# TJMakes_Xiao_Adapter.net
KiCad netlist of a schematic drawn in EasyEDA Pro
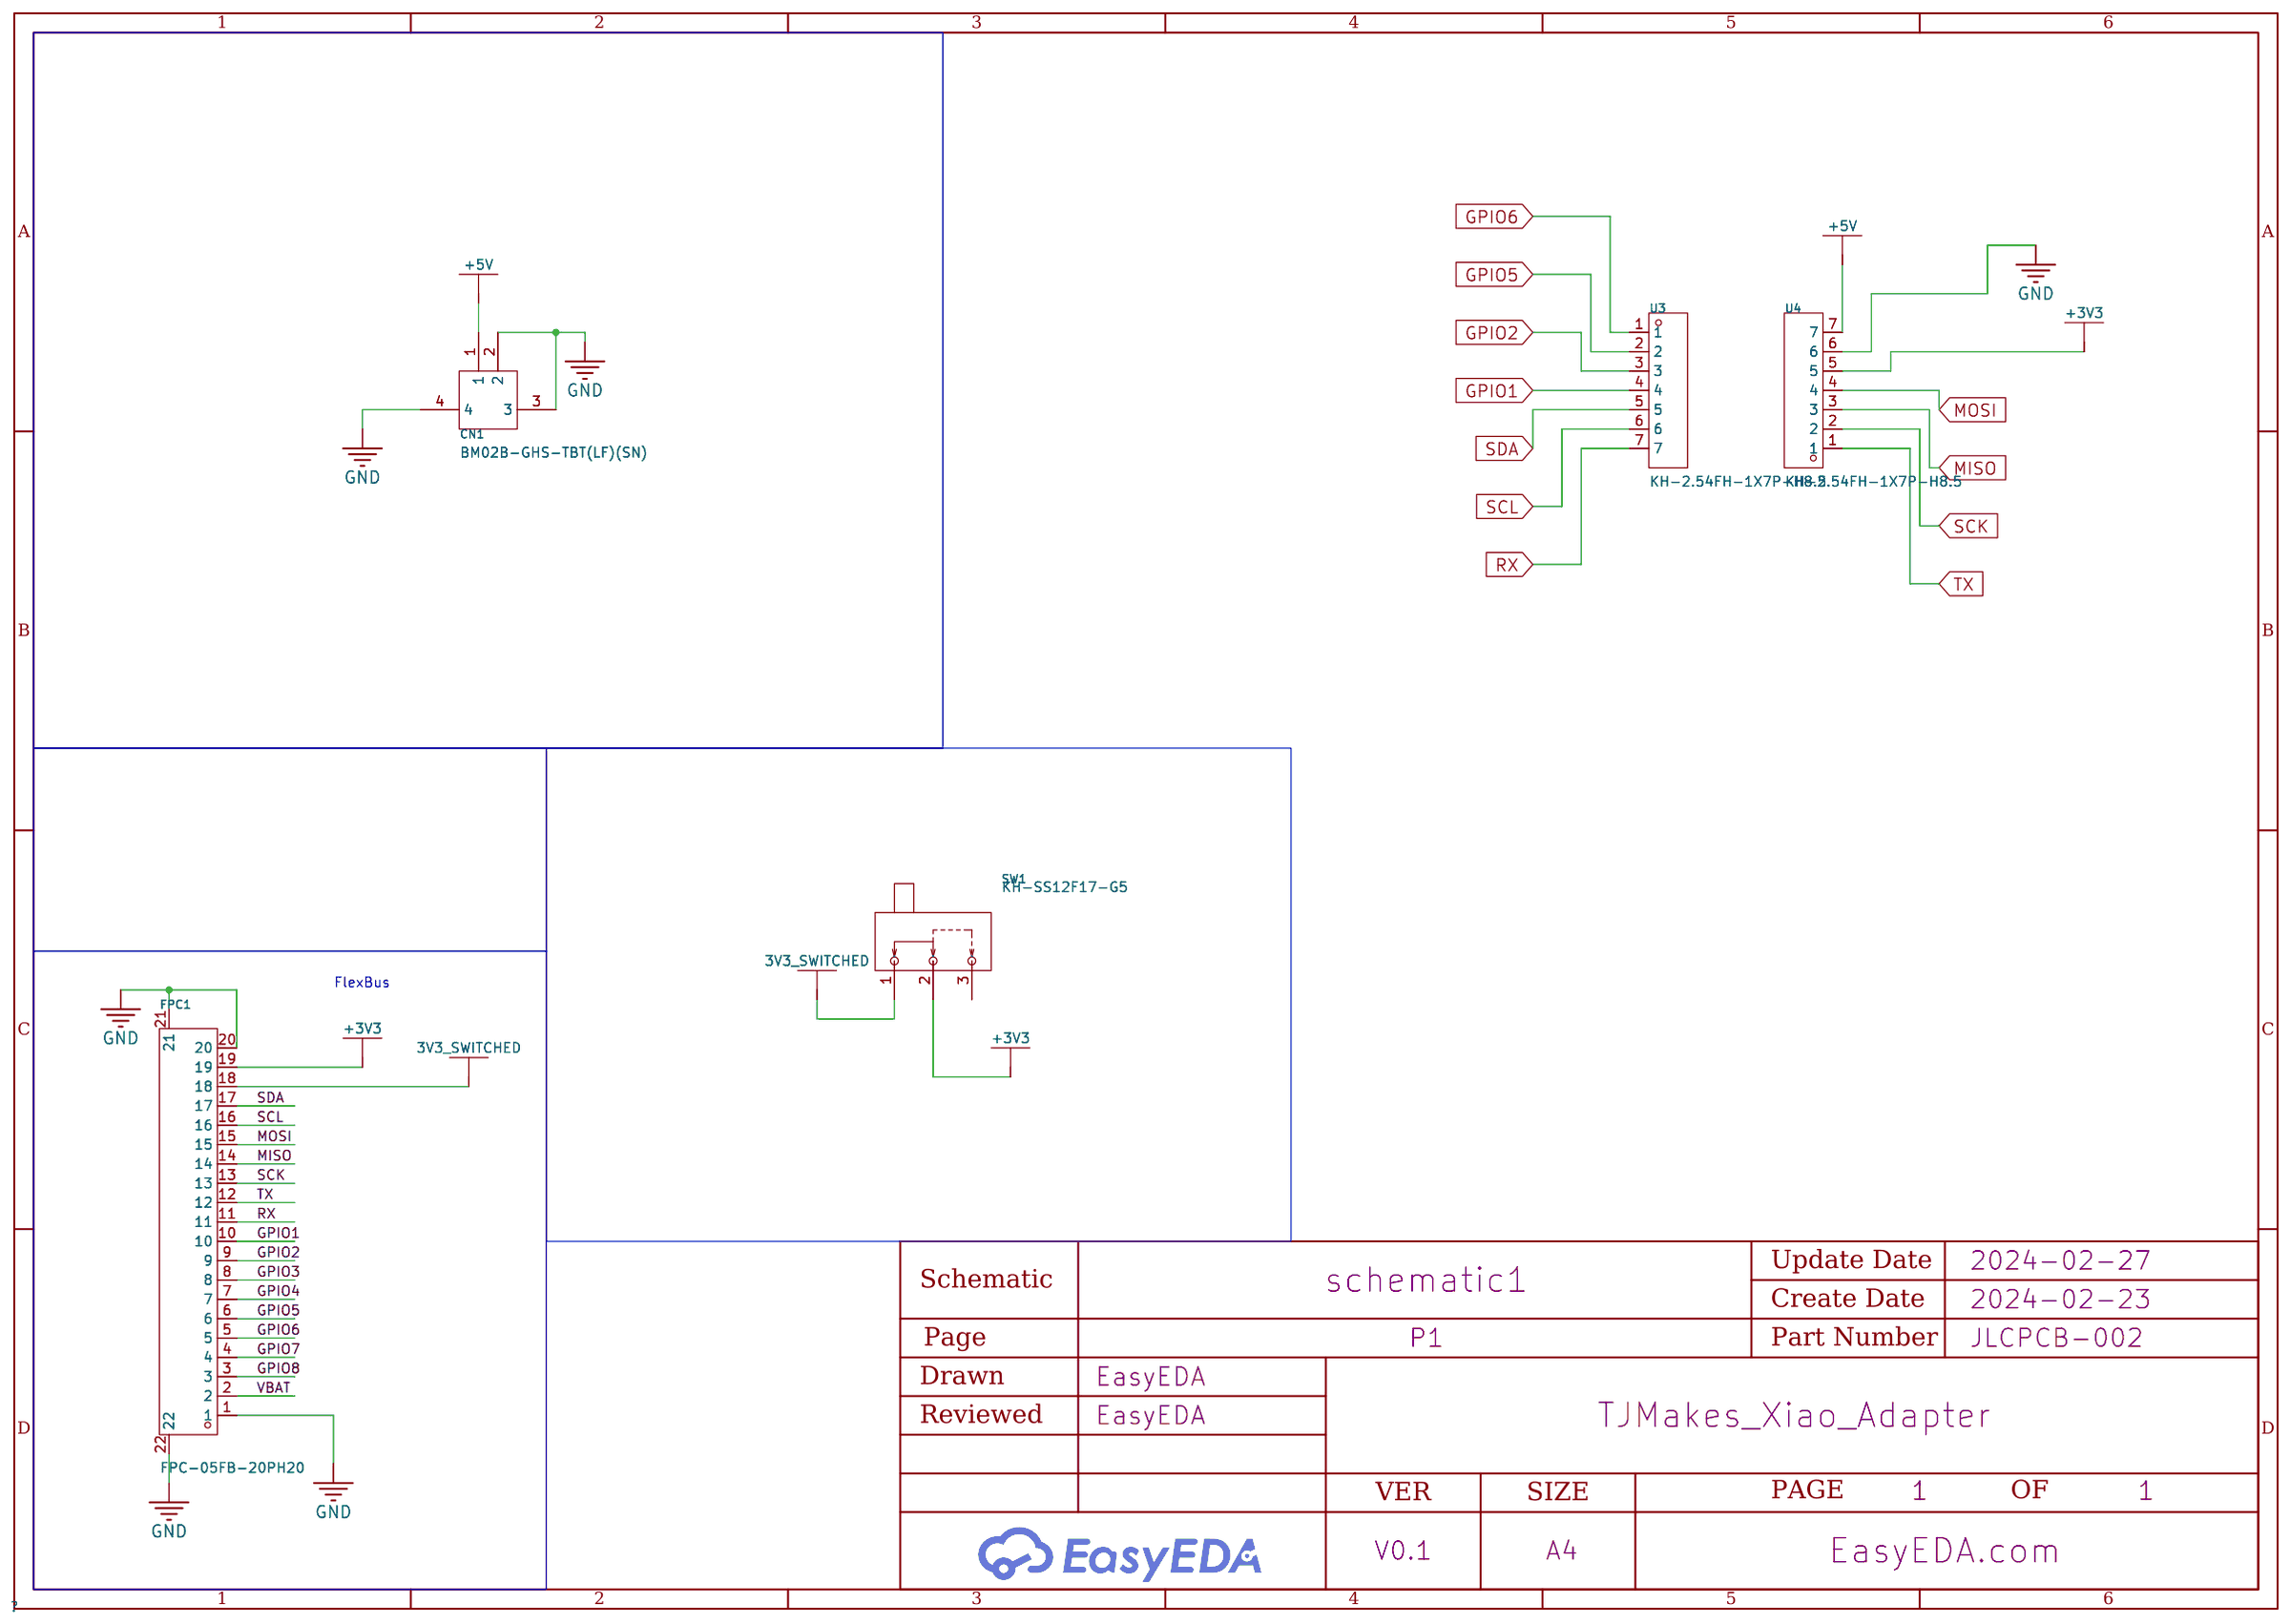
[diagram p0: schematic sheet]

(export (version "E")
  (design (tool "Eeschema 10.0.6"))
  (components
    (comp (ref "CN1")
      (value "BM02B-GHS-TBT(LF)(SN)")
      (footprint "easyedapro:CONN-SMD_2P-P1.25_BM02B-GHS-TBT-LF-SN")
      (fields (field (name "Manufacturer") "JST"))
      (libsource (lib "easyedapro") (part "BM02B-GHS-TBT (LF)(SN)"))
    )
    (comp (ref "FPC1")
      (value "FPC-05FB-20PH20")
      (footprint "easyedapro:FPC-SMD_20P-P0.50_FPC-05FB-20PH20")
      (fields (field (name "Manufacturer") "XUNPU(讯普)"))
      (libsource (lib "easyedapro") (part "FPC-05FB-20PH20"))
    )
    (comp (ref "SW1")
      (value "KH-SS12F17-G5")
      (footprint "easyedapro:SW-TH_KH-SS12F17-G5")
      (fields (field (name "Manufacturer") "kinghelm(金航标)"))
      (libsource (lib "easyedapro") (part "KH-SS12F17-G5"))
    )
    (comp (ref "U3")
      (value "KH-2.54FH-1X7P-H8.5")
      (footprint "easyedapro:HDR-TH_7P-P2.54-V-F")
      (fields (field (name "Manufacturer") "kinghelm(金航标)"))
      (libsource (lib "easyedapro") (part "KH-2.54FH-1X7P-H8.5"))
    )
    (comp (ref "U4")
      (value "KH-2.54FH-1X7P-H8.5")
      (footprint "easyedapro:HDR-TH_7P-P2.54-V-F")
      (fields (field (name "Manufacturer") "kinghelm(金航标)"))
      (libsource (lib "easyedapro") (part "KH-2.54FH-1X7P-H8.5"))
    )
  )
  (nets
    (net (code "1") (name "+3V3") (class "Default")
      (node (ref "FPC1") (pin "19") (pinfunction "19_19") (pintype "input"))
      (node (ref "SW1") (pin "2") (pinfunction "2_2") (pintype "input"))
      (node (ref "U4") (pin "5") (pinfunction "5_5") (pintype "input"))
    )
    (net (code "2") (name "+5V") (class "Default")
      (node (ref "CN1") (pin "1") (pinfunction "1_1") (pintype "input"))
      (node (ref "U4") (pin "7") (pinfunction "7_7") (pintype "input"))
    )
    (net (code "3") (name "/GPIO3") (class "Default")
      (node (ref "FPC1") (pin "8") (pinfunction "8_8") (pintype "input"))
    )
    (net (code "4") (name "/GPIO4") (class "Default")
      (node (ref "FPC1") (pin "7") (pinfunction "7_7") (pintype "input"))
    )
    (net (code "5") (name "/GPIO7") (class "Default")
      (node (ref "FPC1") (pin "4") (pinfunction "4_4") (pintype "input"))
    )
    (net (code "6") (name "/GPIO8") (class "Default")
      (node (ref "FPC1") (pin "3") (pinfunction "3_3") (pintype "input"))
    )
    (net (code "7") (name "/VBAT") (class "Default")
      (node (ref "FPC1") (pin "2") (pinfunction "2_2") (pintype "input"))
    )
    (net (code "8") (name "3V3_SWITCHED") (class "Default")
      (node (ref "FPC1") (pin "18") (pinfunction "18_18") (pintype "input"))
      (node (ref "SW1") (pin "1") (pinfunction "1_1") (pintype "input"))
    )
    (net (code "9") (name "GND") (class "Default")
      (node (ref "CN1") (pin "2") (pinfunction "2_2") (pintype "input"))
      (node (ref "CN1") (pin "3") (pinfunction "3_3") (pintype "input"))
      (node (ref "CN1") (pin "4") (pinfunction "4_4") (pintype "input"))
      (node (ref "FPC1") (pin "1") (pinfunction "1_1") (pintype "input"))
      (node (ref "FPC1") (pin "20") (pinfunction "20_20") (pintype "input"))
      (node (ref "FPC1") (pin "21") (pinfunction "21_21") (pintype "input"))
      (node (ref "FPC1") (pin "22") (pinfunction "22_22") (pintype "input"))
      (node (ref "U4") (pin "6") (pinfunction "6_6") (pintype "input"))
    )
    (net (code "10") (name "GPIO1") (class "Default")
      (node (ref "FPC1") (pin "10") (pinfunction "10_10") (pintype "input"))
      (node (ref "U3") (pin "4") (pinfunction "4_4") (pintype "input"))
    )
    (net (code "11") (name "GPIO2") (class "Default")
      (node (ref "FPC1") (pin "9") (pinfunction "9_9") (pintype "input"))
      (node (ref "U3") (pin "3") (pinfunction "3_3") (pintype "input"))
    )
    (net (code "12") (name "GPIO5") (class "Default")
      (node (ref "FPC1") (pin "6") (pinfunction "6_6") (pintype "input"))
      (node (ref "U3") (pin "2") (pinfunction "2_2") (pintype "input"))
    )
    (net (code "13") (name "GPIO6") (class "Default")
      (node (ref "FPC1") (pin "5") (pinfunction "5_5") (pintype "input"))
      (node (ref "U3") (pin "1") (pinfunction "1_1") (pintype "input"))
    )
    (net (code "14") (name "MISO") (class "Default")
      (node (ref "FPC1") (pin "14") (pinfunction "14_14") (pintype "input"))
      (node (ref "U4") (pin "3") (pinfunction "3_3") (pintype "input"))
    )
    (net (code "15") (name "MOSI") (class "Default")
      (node (ref "FPC1") (pin "15") (pinfunction "15_15") (pintype "input"))
      (node (ref "U4") (pin "4") (pinfunction "4_4") (pintype "input"))
    )
    (net (code "16") (name "RX") (class "Default")
      (node (ref "FPC1") (pin "11") (pinfunction "11_11") (pintype "input"))
      (node (ref "U3") (pin "7") (pinfunction "7_7") (pintype "input"))
    )
    (net (code "17") (name "SCK") (class "Default")
      (node (ref "FPC1") (pin "13") (pinfunction "13_13") (pintype "input"))
      (node (ref "U4") (pin "2") (pinfunction "2_2") (pintype "input"))
    )
    (net (code "18") (name "SCL") (class "Default")
      (node (ref "FPC1") (pin "16") (pinfunction "16_16") (pintype "input"))
      (node (ref "U3") (pin "6") (pinfunction "6_6") (pintype "input"))
    )
    (net (code "19") (name "SDA") (class "Default")
      (node (ref "FPC1") (pin "17") (pinfunction "17_17") (pintype "input"))
      (node (ref "U3") (pin "5") (pinfunction "5_5") (pintype "input"))
    )
    (net (code "20") (name "TX") (class "Default")
      (node (ref "FPC1") (pin "12") (pinfunction "12_12") (pintype "input"))
      (node (ref "U4") (pin "1") (pinfunction "1_1") (pintype "input"))
    )
    (net (code "21") (name "unconnected-(SW1-Pad3)") (class "Default")
      (node (ref "SW1") (pin "3") (pinfunction "3_3") (pintype "input"))
    )
  )
)
